# Project.net
KiCad netlist of a schematic drawn in EasyEDA Pro
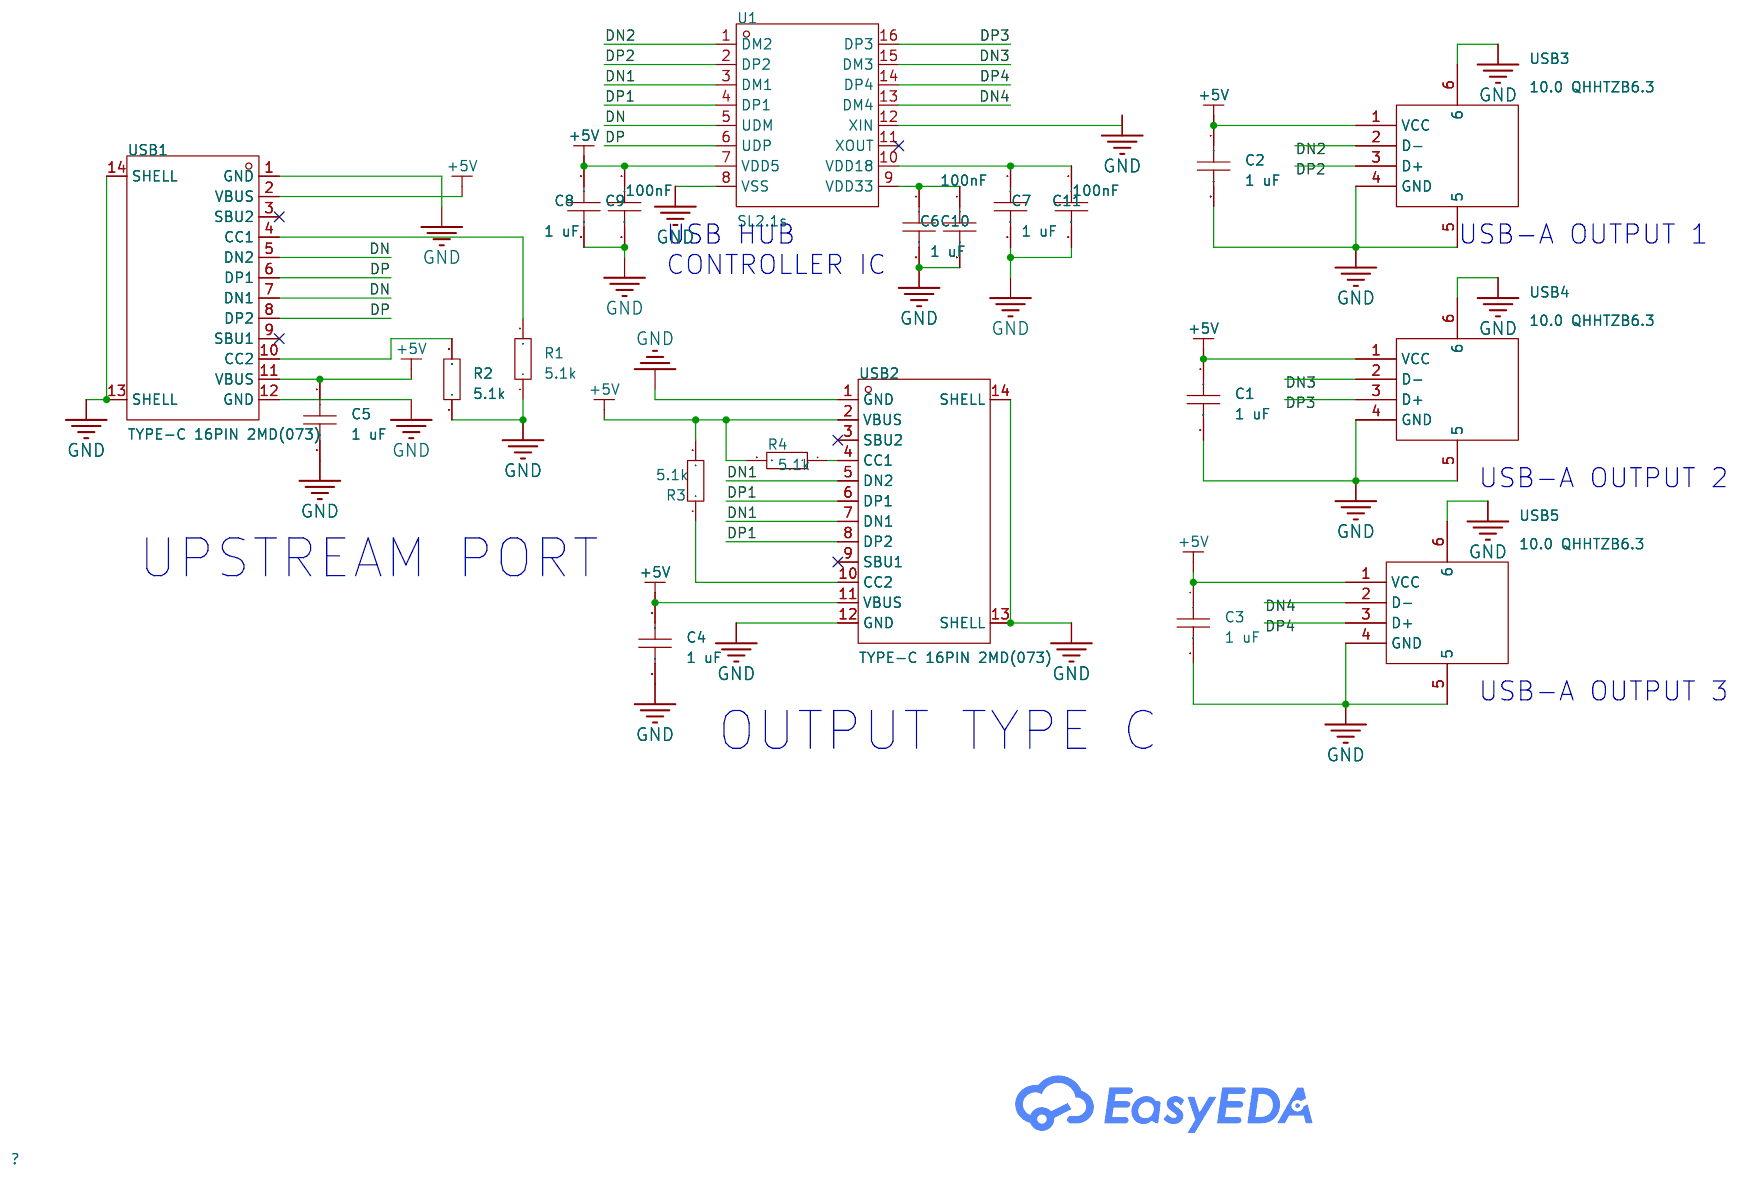
[diagram p0: schematic sheet]

(export (version "E")
  (design (tool "Eeschema 10.0.6"))
  (components
    (comp (ref "C1")
      (value "1 uF")
      (footprint "easyedapro:C0603")
      (libsource (lib "easyedapro") (part "CAP"))
    )
    (comp (ref "C2")
      (value "1 uF")
      (footprint "easyedapro:C0603")
      (libsource (lib "easyedapro") (part "CAP"))
    )
    (comp (ref "C3")
      (value "1 uF")
      (footprint "easyedapro:C0603")
      (libsource (lib "easyedapro") (part "CAP"))
    )
    (comp (ref "C4")
      (value "1 uF")
      (footprint "easyedapro:C0603")
      (libsource (lib "easyedapro") (part "CAP"))
    )
    (comp (ref "C5")
      (value "1 uF")
      (footprint "easyedapro:C0603")
      (libsource (lib "easyedapro") (part "CAP"))
    )
    (comp (ref "C6")
      (value "1 uF")
      (footprint "easyedapro:C0603")
      (libsource (lib "easyedapro") (part "CAP"))
    )
    (comp (ref "C7")
      (value "1 uF")
      (footprint "easyedapro:C0603")
      (libsource (lib "easyedapro") (part "CAP"))
    )
    (comp (ref "C8")
      (value "1 uF")
      (footprint "easyedapro:C0603")
      (libsource (lib "easyedapro") (part "CAP"))
    )
    (comp (ref "C9")
      (value "100nF")
      (footprint "easyedapro:C0603")
      (libsource (lib "easyedapro") (part "CAP"))
    )
    (comp (ref "C10")
      (value "100nF")
      (footprint "easyedapro:C0603")
      (libsource (lib "easyedapro") (part "CAP"))
    )
    (comp (ref "C11")
      (value "100nF")
      (footprint "easyedapro:C0603")
      (libsource (lib "easyedapro") (part "CAP"))
    )
    (comp (ref "R1")
      (value "5.1k")
      (footprint "easyedapro:R0603")
      (libsource (lib "easyedapro") (part "Res"))
    )
    (comp (ref "R2")
      (value "5.1k")
      (footprint "easyedapro:R0603")
      (libsource (lib "easyedapro") (part "Res"))
    )
    (comp (ref "R3")
      (value "5.1k")
      (footprint "easyedapro:R0603")
      (libsource (lib "easyedapro") (part "Res"))
    )
    (comp (ref "R4")
      (value "5.1k")
      (footprint "easyedapro:R0603")
      (libsource (lib "easyedapro") (part "Res"))
    )
    (comp (ref "U1")
      (value "SL2.1s")
      (footprint "easyedapro:SSOP-16_L4.6-W2.6-P0.53-LS4.0-BL")
      (fields (field (name "Manufacturer") "CoreChips(和芯润德)"))
      (libsource (lib "easyedapro") (part "SL2.1S"))
    )
    (comp (ref "USB1")
      (value "TYPE-C 16PIN 2MD(073)")
      (footprint "easyedapro:USB-C-SMD_TYPE-C-6PIN-2MD-073")
      (fields (field (name "Manufacturer") "SHOU HAN(首韩)"))
      (libsource (lib "easyedapro") (part "TYPE-C 16PIN 2MD(073)"))
    )
    (comp (ref "USB2")
      (value "TYPE-C 16PIN 2MD(073)")
      (footprint "easyedapro:USB-C-SMD_TYPE-C-6PIN-2MD-073")
      (fields (field (name "Manufacturer") "SHOU HAN(首韩)"))
      (libsource (lib "easyedapro") (part "TYPE-C 16PIN 2MD(073)"))
    )
    (comp (ref "USB3")
      (value "10.0 QHHTZB6.3")
      (footprint "easyedapro:USB-A-TH_10.0QHHTZB6.3")
      (fields (field (name "Manufacturer") "SHOU HAN(首韩)"))
      (libsource (lib "easyedapro") (part "10.0 QHHTZB6.3"))
    )
    (comp (ref "USB4")
      (value "10.0 QHHTZB6.3")
      (footprint "easyedapro:USB-A-TH_10.0QHHTZB6.3")
      (fields (field (name "Manufacturer") "SHOU HAN(首韩)"))
      (libsource (lib "easyedapro") (part "10.0 QHHTZB6.3"))
    )
    (comp (ref "USB5")
      (value "10.0 QHHTZB6.3")
      (footprint "easyedapro:USB-A-TH_10.0QHHTZB6.3")
      (fields (field (name "Manufacturer") "SHOU HAN(首韩)"))
      (libsource (lib "easyedapro") (part "10.0 QHHTZB6.3"))
    )
  )
  (nets
    (net (code "1") (name "+5V") (class "Default")
      (node (ref "C1") (pin "1") (pinfunction "1_1") (pintype "input"))
      (node (ref "C2") (pin "1") (pinfunction "1_1") (pintype "input"))
      (node (ref "C3") (pin "1") (pinfunction "1_1") (pintype "input"))
      (node (ref "C4") (pin "1") (pinfunction "1_1") (pintype "input"))
      (node (ref "C5") (pin "1") (pinfunction "1_1") (pintype "input"))
      (node (ref "C8") (pin "1") (pinfunction "1_1") (pintype "input"))
      (node (ref "C9") (pin "1") (pinfunction "1_1") (pintype "input"))
      (node (ref "R3") (pin "2") (pinfunction "2_2") (pintype "input"))
      (node (ref "R4") (pin "2") (pinfunction "2_2") (pintype "input"))
      (node (ref "U1") (pin "7") (pinfunction "VDD5_7") (pintype "unspecified"))
      (node (ref "USB1") (pin "11") (pinfunction "VBUS_11") (pintype "unspecified"))
      (node (ref "USB1") (pin "2") (pinfunction "VBUS_2") (pintype "unspecified"))
      (node (ref "USB2") (pin "11") (pinfunction "VBUS_11") (pintype "unspecified"))
      (node (ref "USB2") (pin "2") (pinfunction "VBUS_2") (pintype "unspecified"))
      (node (ref "USB3") (pin "1") (pinfunction "VCC_1") (pintype "unspecified"))
      (node (ref "USB4") (pin "1") (pinfunction "VCC_1") (pintype "unspecified"))
      (node (ref "USB5") (pin "1") (pinfunction "VCC_1") (pintype "unspecified"))
    )
    (net (code "2") (name "/DN") (class "Default")
      (node (ref "U1") (pin "5") (pinfunction "UDM_5") (pintype "unspecified"))
      (node (ref "USB1") (pin "5") (pinfunction "DN2_5") (pintype "unspecified"))
      (node (ref "USB1") (pin "7") (pinfunction "DN1_7") (pintype "unspecified"))
    )
    (net (code "3") (name "/DN1") (class "Default")
      (node (ref "U1") (pin "3") (pinfunction "DM1_3") (pintype "unspecified"))
      (node (ref "USB2") (pin "5") (pinfunction "DN2_5") (pintype "unspecified"))
      (node (ref "USB2") (pin "7") (pinfunction "DN1_7") (pintype "unspecified"))
    )
    (net (code "4") (name "/DN2") (class "Default")
      (node (ref "U1") (pin "1") (pinfunction "DM2_1") (pintype "unspecified"))
      (node (ref "USB3") (pin "2") (pinfunction "D-_2") (pintype "unspecified"))
    )
    (net (code "5") (name "/DN3") (class "Default")
      (node (ref "U1") (pin "15") (pinfunction "DM3_15") (pintype "unspecified"))
      (node (ref "USB4") (pin "2") (pinfunction "D-_2") (pintype "unspecified"))
    )
    (net (code "6") (name "/DN4") (class "Default")
      (node (ref "U1") (pin "13") (pinfunction "DM4_13") (pintype "unspecified"))
      (node (ref "USB5") (pin "2") (pinfunction "D-_2") (pintype "unspecified"))
    )
    (net (code "7") (name "/DP") (class "Default")
      (node (ref "U1") (pin "6") (pinfunction "UDP_6") (pintype "unspecified"))
      (node (ref "USB1") (pin "6") (pinfunction "DP1_6") (pintype "unspecified"))
      (node (ref "USB1") (pin "8") (pinfunction "DP2_8") (pintype "unspecified"))
    )
    (net (code "8") (name "/DP1") (class "Default")
      (node (ref "U1") (pin "4") (pinfunction "DP1_4") (pintype "unspecified"))
      (node (ref "USB2") (pin "6") (pinfunction "DP1_6") (pintype "unspecified"))
      (node (ref "USB2") (pin "8") (pinfunction "DP2_8") (pintype "unspecified"))
    )
    (net (code "9") (name "/DP2") (class "Default")
      (node (ref "U1") (pin "2") (pinfunction "DP2_2") (pintype "unspecified"))
      (node (ref "USB3") (pin "3") (pinfunction "D+_3") (pintype "unspecified"))
    )
    (net (code "10") (name "/DP3") (class "Default")
      (node (ref "U1") (pin "16") (pinfunction "DP3_16") (pintype "unspecified"))
      (node (ref "USB4") (pin "3") (pinfunction "D+_3") (pintype "unspecified"))
    )
    (net (code "11") (name "/DP4") (class "Default")
      (node (ref "U1") (pin "14") (pinfunction "DP4_14") (pintype "unspecified"))
      (node (ref "USB5") (pin "3") (pinfunction "D+_3") (pintype "unspecified"))
    )
    (net (code "12") (name "GND") (class "Default")
      (node (ref "C1") (pin "2") (pinfunction "2_2") (pintype "input"))
      (node (ref "C10") (pin "2") (pinfunction "2_2") (pintype "input"))
      (node (ref "C11") (pin "2") (pinfunction "2_2") (pintype "input"))
      (node (ref "C2") (pin "2") (pinfunction "2_2") (pintype "input"))
      (node (ref "C3") (pin "2") (pinfunction "2_2") (pintype "input"))
      (node (ref "C4") (pin "2") (pinfunction "2_2") (pintype "input"))
      (node (ref "C5") (pin "2") (pinfunction "2_2") (pintype "input"))
      (node (ref "C6") (pin "2") (pinfunction "2_2") (pintype "input"))
      (node (ref "C7") (pin "2") (pinfunction "2_2") (pintype "input"))
      (node (ref "C8") (pin "2") (pinfunction "2_2") (pintype "input"))
      (node (ref "C9") (pin "2") (pinfunction "2_2") (pintype "input"))
      (node (ref "R1") (pin "1") (pinfunction "1_1") (pintype "input"))
      (node (ref "R2") (pin "1") (pinfunction "1_1") (pintype "input"))
      (node (ref "U1") (pin "12") (pinfunction "XIN_12") (pintype "unspecified"))
      (node (ref "U1") (pin "8") (pinfunction "VSS_8") (pintype "unspecified"))
      (node (ref "USB1") (pin "1") (pinfunction "GND_1") (pintype "unspecified"))
      (node (ref "USB1") (pin "12") (pinfunction "GND_12") (pintype "unspecified"))
      (node (ref "USB1") (pin "13") (pinfunction "SHELL_13") (pintype "unspecified"))
      (node (ref "USB1") (pin "14") (pinfunction "SHELL_14") (pintype "unspecified"))
      (node (ref "USB2") (pin "1") (pinfunction "GND_1") (pintype "unspecified"))
      (node (ref "USB2") (pin "12") (pinfunction "GND_12") (pintype "unspecified"))
      (node (ref "USB2") (pin "13") (pinfunction "SHELL_13") (pintype "unspecified"))
      (node (ref "USB2") (pin "14") (pinfunction "SHELL_14") (pintype "unspecified"))
      (node (ref "USB3") (pin "4") (pinfunction "GND_4") (pintype "unspecified"))
      (node (ref "USB3") (pin "5") (pinfunction "5_5") (pintype "unspecified"))
      (node (ref "USB3") (pin "6") (pinfunction "6_6") (pintype "unspecified"))
      (node (ref "USB4") (pin "4") (pinfunction "GND_4") (pintype "unspecified"))
      (node (ref "USB4") (pin "5") (pinfunction "5_5") (pintype "unspecified"))
      (node (ref "USB4") (pin "6") (pinfunction "6_6") (pintype "unspecified"))
      (node (ref "USB5") (pin "4") (pinfunction "GND_4") (pintype "unspecified"))
      (node (ref "USB5") (pin "5") (pinfunction "5_5") (pintype "unspecified"))
      (node (ref "USB5") (pin "6") (pinfunction "6_6") (pintype "unspecified"))
    )
    (net (code "13") (name "Net-(U1-VDD18)") (class "Default")
      (node (ref "C11") (pin "1") (pinfunction "1_1") (pintype "input"))
      (node (ref "C7") (pin "1") (pinfunction "1_1") (pintype "input"))
      (node (ref "U1") (pin "10") (pinfunction "VDD18_10") (pintype "unspecified"))
    )
    (net (code "14") (name "Net-(U1-VDD33)") (class "Default")
      (node (ref "C10") (pin "1") (pinfunction "1_1") (pintype "input"))
      (node (ref "C6") (pin "1") (pinfunction "1_1") (pintype "input"))
      (node (ref "U1") (pin "9") (pinfunction "VDD33_9") (pintype "unspecified"))
    )
    (net (code "15") (name "Net-(USB1-CC1)") (class "Default")
      (node (ref "R1") (pin "2") (pinfunction "2_2") (pintype "input"))
      (node (ref "USB1") (pin "4") (pinfunction "CC1_4") (pintype "unspecified"))
    )
    (net (code "16") (name "Net-(USB1-CC2)") (class "Default")
      (node (ref "R2") (pin "2") (pinfunction "2_2") (pintype "input"))
      (node (ref "USB1") (pin "10") (pinfunction "CC2_10") (pintype "unspecified"))
    )
    (net (code "17") (name "Net-(USB2-CC1)") (class "Default")
      (node (ref "R4") (pin "1") (pinfunction "1_1") (pintype "input"))
      (node (ref "USB2") (pin "4") (pinfunction "CC1_4") (pintype "unspecified"))
    )
    (net (code "18") (name "Net-(USB2-CC2)") (class "Default")
      (node (ref "R3") (pin "1") (pinfunction "1_1") (pintype "input"))
      (node (ref "USB2") (pin "10") (pinfunction "CC2_10") (pintype "unspecified"))
    )
    (net (code "19") (name "unconnected-(U1-XOUT-Pad11)") (class "Default")
      (node (ref "U1") (pin "11") (pinfunction "XOUT_11") (pintype "unspecified+no_connect"))
    )
    (net (code "20") (name "unconnected-(USB1-SBU1-Pad9)") (class "Default")
      (node (ref "USB1") (pin "9") (pinfunction "SBU1_9") (pintype "unspecified+no_connect"))
    )
    (net (code "21") (name "unconnected-(USB1-SBU2-Pad3)") (class "Default")
      (node (ref "USB1") (pin "3") (pinfunction "SBU2_3") (pintype "unspecified+no_connect"))
    )
    (net (code "22") (name "unconnected-(USB2-SBU1-Pad9)") (class "Default")
      (node (ref "USB2") (pin "9") (pinfunction "SBU1_9") (pintype "unspecified+no_connect"))
    )
    (net (code "23") (name "unconnected-(USB2-SBU2-Pad3)") (class "Default")
      (node (ref "USB2") (pin "3") (pinfunction "SBU2_3") (pintype "unspecified+no_connect"))
    )
  )
)
